# mainboard_v1.net
KiCad netlist of a schematic drawn in EAGLE
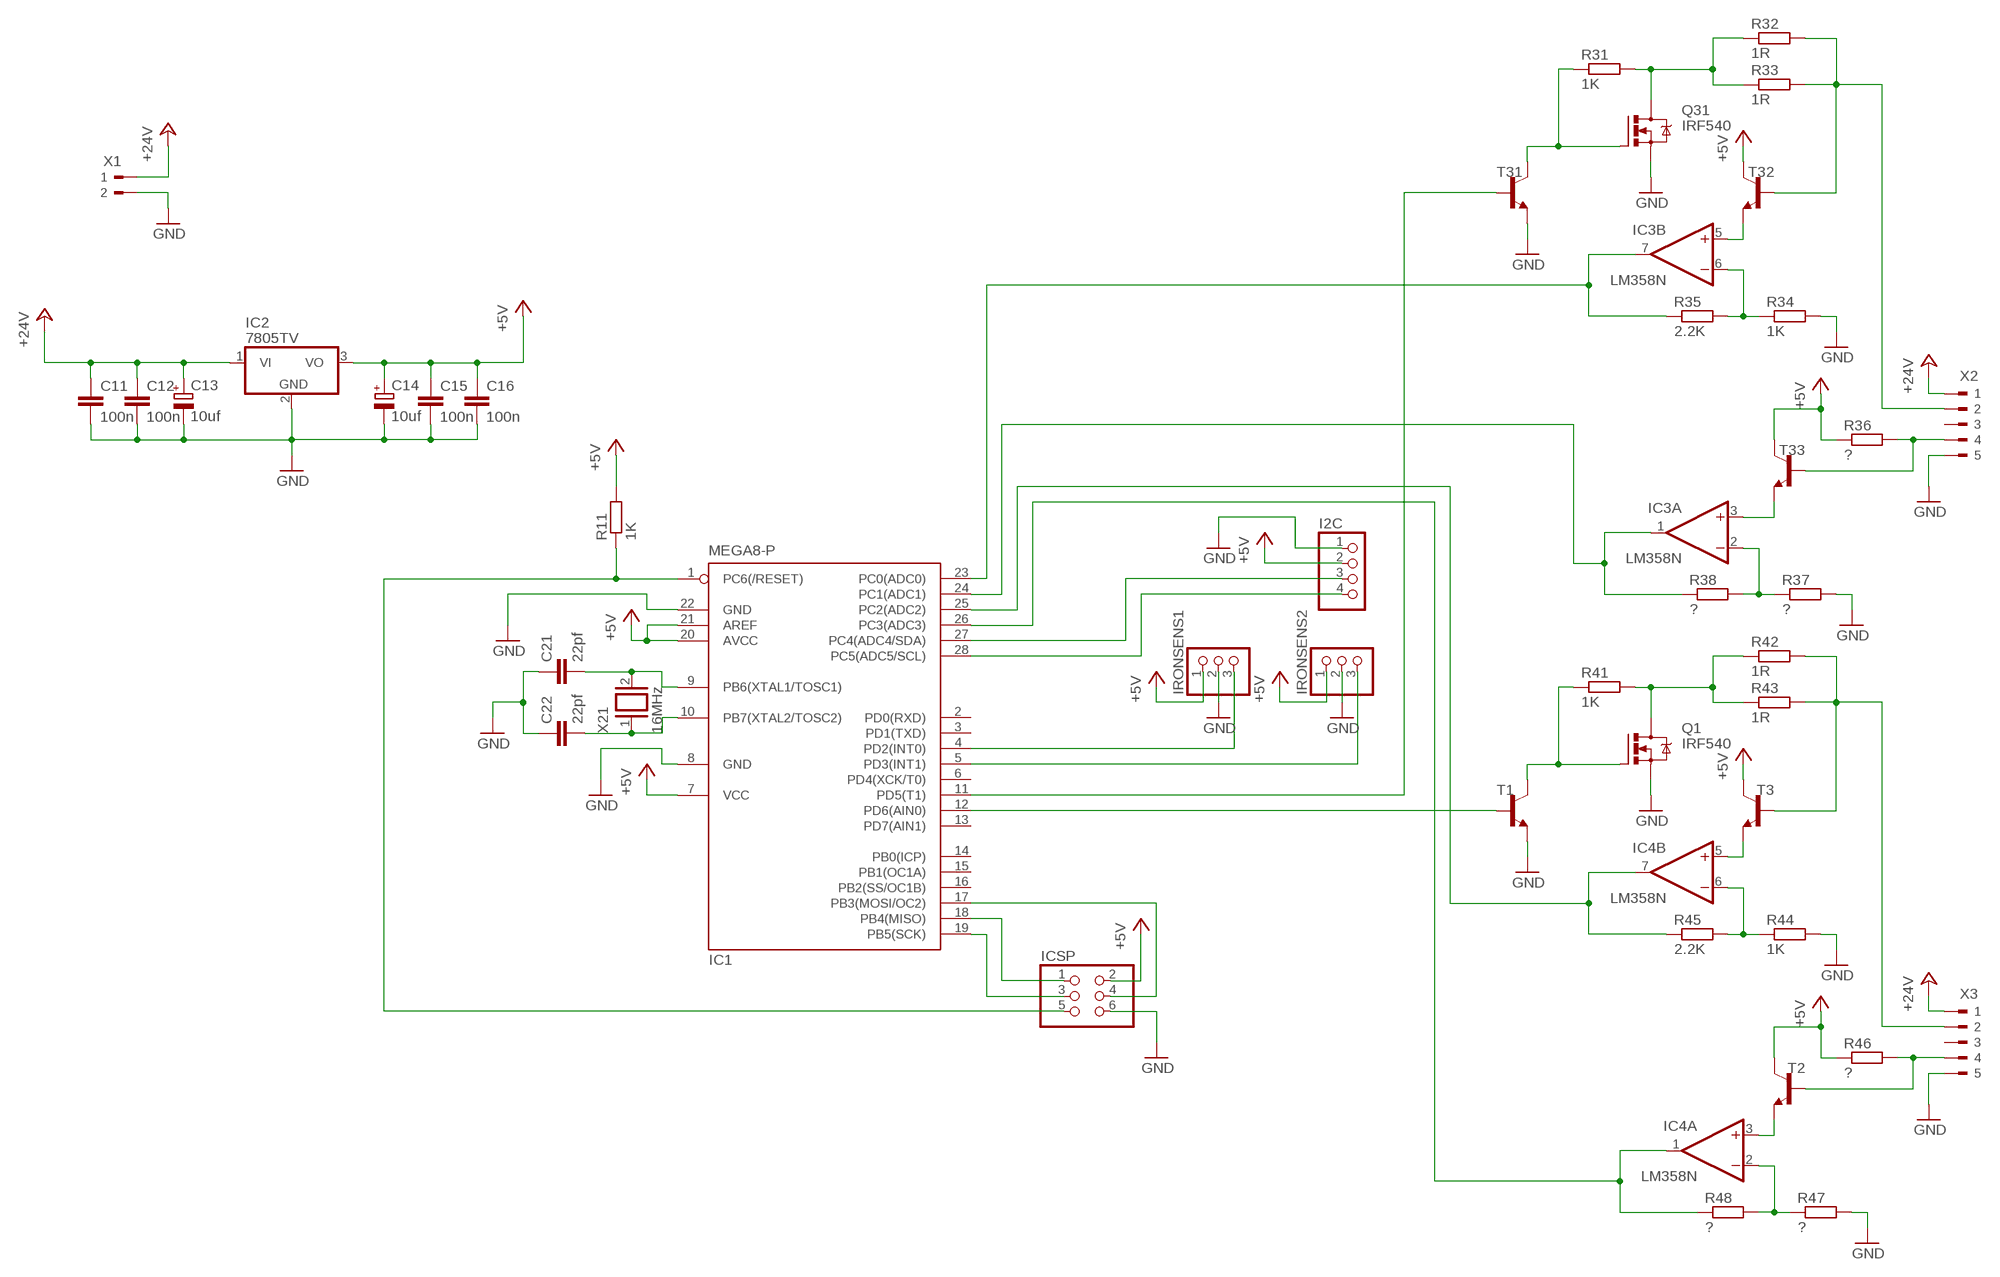
[diagram p0: schematic, sheet 1]

(export (version "E")
  (design (tool "Eeschema 10.0.6"))
  (components
    (comp (ref "C11")
      (value "100n")
      (footprint "eagle-import:C050-030X075")
      (libsource (lib "eagle-import") (part "C-EU050-030X075"))
    )
    (comp (ref "C12")
      (value "100n")
      (footprint "eagle-import:C025-024X044")
      (libsource (lib "eagle-import") (part "C-EU025-024X044"))
    )
    (comp (ref "C13")
      (value "10uf")
      (footprint "eagle-import:E2,5-6E")
      (libsource (lib "eagle-import") (part "CPOL-EUE2,5-6E"))
    )
    (comp (ref "C14")
      (value "10uf")
      (footprint "eagle-import:E2,5-6E")
      (libsource (lib "eagle-import") (part "CPOL-EUE2,5-6E"))
    )
    (comp (ref "C15")
      (value "100n")
      (footprint "eagle-import:C025-024X044")
      (libsource (lib "eagle-import") (part "C-EU025-024X044"))
    )
    (comp (ref "C16")
      (value "100n")
      (footprint "eagle-import:C050-030X075")
      (libsource (lib "eagle-import") (part "C-EU050-030X075"))
    )
    (comp (ref "C21")
      (value "22pf")
      (footprint "eagle-import:C025-025X050")
      (libsource (lib "eagle-import") (part "C-EU025-025X050"))
    )
    (comp (ref "C22")
      (value "22pf")
      (footprint "eagle-import:C025-025X050")
      (libsource (lib "eagle-import") (part "C-EU025-025X050"))
    )
    (comp (ref "I2C")
      (value "PINHD-1X4")
      (footprint "eagle-import:1X04")
      (libsource (lib "eagle-import") (part "PINHD-1X4"))
    )
    (comp (ref "IC1")
      (value "MEGA8-P")
      (footprint "eagle-import:DIL28-3")
      (libsource (lib "eagle-import") (part "MEGA8-P"))
    )
    (comp (ref "IC2")
      (value "7805TV")
      (footprint "eagle-import:TO220V")
      (libsource (lib "eagle-import") (part "78TV05"))
    )
    (comp (ref "IC3")
      (value "LM358N")
      (footprint "eagle-import:DIL08")
      (libsource (lib "eagle-import") (part "LM358N"))
    )
    (comp (ref "IC4")
      (value "LM358N")
      (footprint "eagle-import:DIL08")
      (libsource (lib "eagle-import") (part "LM358N"))
    )
    (comp (ref "ICSP")
      (value "PINHD-2X3")
      (footprint "eagle-import:2X03")
      (libsource (lib "eagle-import") (part "PINHD-2X3"))
    )
    (comp (ref "IRONSENS1")
      (value "PINHD-1X3")
      (footprint "eagle-import:1X03")
      (libsource (lib "eagle-import") (part "PINHD-1X3"))
    )
    (comp (ref "IRONSENS2")
      (value "PINHD-1X3")
      (footprint "eagle-import:1X03")
      (libsource (lib "eagle-import") (part "PINHD-1X3"))
    )
    (comp (ref "Q1")
      (value "IRF540")
      (footprint "eagle-import:TO220BV")
      (libsource (lib "eagle-import") (part "IRF540"))
    )
    (comp (ref "Q31")
      (value "IRF540")
      (footprint "eagle-import:TO220BV")
      (libsource (lib "eagle-import") (part "IRF540"))
    )
    (comp (ref "R11")
      (value "1K")
      (footprint "eagle-import:0204_7")
      (libsource (lib "eagle-import") (part "R-EU_0204/7"))
    )
    (comp (ref "R31")
      (value "1K")
      (footprint "eagle-import:0204_7")
      (libsource (lib "eagle-import") (part "R-EU_0204/7"))
    )
    (comp (ref "R32")
      (value "1R")
      (footprint "eagle-import:R2512")
      (libsource (lib "eagle-import") (part "R-EU_R2512"))
    )
    (comp (ref "R33")
      (value "1R")
      (footprint "eagle-import:0204_7")
      (libsource (lib "eagle-import") (part "R-EU_0204/7"))
    )
    (comp (ref "R34")
      (value "1K")
      (footprint "eagle-import:0204_7")
      (libsource (lib "eagle-import") (part "R-EU_0204/7"))
    )
    (comp (ref "R35")
      (value "2.2K")
      (footprint "eagle-import:0204_7")
      (libsource (lib "eagle-import") (part "R-EU_0204/7"))
    )
    (comp (ref "R36")
      (value "?")
      (footprint "eagle-import:0204_7")
      (libsource (lib "eagle-import") (part "R-EU_0204/7"))
    )
    (comp (ref "R37")
      (value "?")
      (footprint "eagle-import:0204_7")
      (libsource (lib "eagle-import") (part "R-EU_0204/7"))
    )
    (comp (ref "R38")
      (value "?")
      (footprint "eagle-import:0204_7")
      (libsource (lib "eagle-import") (part "R-EU_0204/7"))
    )
    (comp (ref "R41")
      (value "1K")
      (footprint "eagle-import:0204_7")
      (libsource (lib "eagle-import") (part "R-EU_0204/7"))
    )
    (comp (ref "R42")
      (value "1R")
      (footprint "eagle-import:R2512")
      (libsource (lib "eagle-import") (part "R-EU_R2512"))
    )
    (comp (ref "R43")
      (value "1R")
      (footprint "eagle-import:0204_7")
      (libsource (lib "eagle-import") (part "R-EU_0204/7"))
    )
    (comp (ref "R44")
      (value "1K")
      (footprint "eagle-import:0204_7")
      (libsource (lib "eagle-import") (part "R-EU_0204/7"))
    )
    (comp (ref "R45")
      (value "2.2K")
      (footprint "eagle-import:0204_7")
      (libsource (lib "eagle-import") (part "R-EU_0204/7"))
    )
    (comp (ref "R46")
      (value "?")
      (footprint "eagle-import:0204_7")
      (libsource (lib "eagle-import") (part "R-EU_0204/7"))
    )
    (comp (ref "R47")
      (value "?")
      (footprint "eagle-import:0204_7")
      (libsource (lib "eagle-import") (part "R-EU_0204/7"))
    )
    (comp (ref "R48")
      (value "?")
      (footprint "eagle-import:0204_7")
      (libsource (lib "eagle-import") (part "R-EU_0204/7"))
    )
    (comp (ref "T1")
      (value "BC548-NPN-TO92-CBE")
      (footprint "eagle-import:TO92-CBE")
      (libsource (lib "eagle-import") (part "-NPN-TO92-CBEBC548"))
    )
    (comp (ref "T2")
      (value "BC548-NPN-TO92-CBE")
      (footprint "eagle-import:TO92-CBE")
      (libsource (lib "eagle-import") (part "-NPN-TO92-CBEBC548"))
    )
    (comp (ref "T3")
      (value "BC548-NPN-TO92-CBE")
      (footprint "eagle-import:TO92-CBE")
      (libsource (lib "eagle-import") (part "-NPN-TO92-CBEBC548"))
    )
    (comp (ref "T31")
      (value "BC548-NPN-TO92-CBE")
      (footprint "eagle-import:TO92-CBE")
      (libsource (lib "eagle-import") (part "-NPN-TO92-CBEBC548"))
    )
    (comp (ref "T32")
      (value "BC548-NPN-TO92-CBE")
      (footprint "eagle-import:TO92-CBE")
      (libsource (lib "eagle-import") (part "-NPN-TO92-CBEBC548"))
    )
    (comp (ref "T33")
      (value "BC548-NPN-TO92-CBE")
      (footprint "eagle-import:TO92-CBE")
      (libsource (lib "eagle-import") (part "-NPN-TO92-CBEBC548"))
    )
    (comp (ref "X1")
      (value "180-2")
      (footprint "eagle-import:180-2")
      (libsource (lib "eagle-import") (part "180-2"))
    )
    (comp (ref "X2")
      (value "180-5")
      (footprint "eagle-import:180-5")
      (libsource (lib "eagle-import") (part "180-5"))
    )
    (comp (ref "X3")
      (value "180-5")
      (footprint "eagle-import:180-5")
      (libsource (lib "eagle-import") (part "180-5"))
    )
    (comp (ref "X21")
      (value "16MHz")
      (footprint "eagle-import:QS")
      (libsource (lib "eagle-import") (part "XTAL/S"))
    )
  )
  (nets
    (net (code "1") (name "+5V") (class "Default")
      (node (ref "C14") (pin "+") (pinfunction "+_+") (pintype "passive"))
      (node (ref "C15") (pin "1") (pinfunction "1_1") (pintype "passive"))
      (node (ref "C16") (pin "1") (pinfunction "1_1") (pintype "passive"))
      (node (ref "I2C") (pin "2") (pinfunction "2_2") (pintype "passive"))
      (node (ref "IC1") (pin "20") (pinfunction "AVCC_20") (pintype "power_in"))
      (node (ref "IC1") (pin "21") (pinfunction "AREF_21") (pintype "passive"))
      (node (ref "IC1") (pin "7") (pinfunction "VCC_7") (pintype "power_in"))
      (node (ref "IC2") (pin "3") (pinfunction "VO_3") (pintype "passive"))
      (node (ref "ICSP") (pin "2") (pinfunction "2_2") (pintype "passive"))
      (node (ref "IRONSENS1") (pin "1") (pinfunction "1_1") (pintype "passive"))
      (node (ref "IRONSENS2") (pin "1") (pinfunction "1_1") (pintype "passive"))
      (node (ref "R11") (pin "2") (pinfunction "2_2") (pintype "passive"))
      (node (ref "R36") (pin "1") (pinfunction "1_1") (pintype "passive"))
      (node (ref "R46") (pin "1") (pinfunction "1_1") (pintype "passive"))
      (node (ref "T2") (pin "C") (pinfunction "C_C") (pintype "passive"))
      (node (ref "T3") (pin "C") (pinfunction "C_C") (pintype "passive"))
      (node (ref "T32") (pin "C") (pinfunction "C_C") (pintype "passive"))
      (node (ref "T33") (pin "C") (pinfunction "C_C") (pintype "passive"))
    )
    (net (code "2") (name "+24V") (class "Default")
      (node (ref "C11") (pin "1") (pinfunction "1_1") (pintype "passive"))
      (node (ref "C12") (pin "1") (pinfunction "1_1") (pintype "passive"))
      (node (ref "C13") (pin "+") (pinfunction "+_+") (pintype "passive"))
      (node (ref "IC2") (pin "1") (pinfunction "VI_1") (pintype "input"))
      (node (ref "X1") (pin "1") (pinfunction "1_1") (pintype "passive"))
      (node (ref "X2") (pin "1") (pinfunction "1_1") (pintype "passive"))
      (node (ref "X3") (pin "1") (pinfunction "1_1") (pintype "passive"))
    )
    (net (code "3") (name "GND") (class "Default")
      (node (ref "C11") (pin "2") (pinfunction "2_2") (pintype "passive"))
      (node (ref "C12") (pin "2") (pinfunction "2_2") (pintype "passive"))
      (node (ref "C13") (pin "-") (pinfunction "-_-") (pintype "passive"))
      (node (ref "C14") (pin "-") (pinfunction "-_-") (pintype "passive"))
      (node (ref "C15") (pin "2") (pinfunction "2_2") (pintype "passive"))
      (node (ref "C16") (pin "2") (pinfunction "2_2") (pintype "passive"))
      (node (ref "C21") (pin "1") (pinfunction "1_1") (pintype "passive"))
      (node (ref "C22") (pin "1") (pinfunction "1_1") (pintype "passive"))
      (node (ref "I2C") (pin "1") (pinfunction "1_1") (pintype "passive"))
      (node (ref "IC1") (pin "22") (pinfunction "GND_22") (pintype "power_in"))
      (node (ref "IC1") (pin "8") (pinfunction "GND_8") (pintype "power_in"))
      (node (ref "IC2") (pin "2") (pinfunction "GND_2") (pintype "passive"))
      (node (ref "ICSP") (pin "6") (pinfunction "6_6") (pintype "passive"))
      (node (ref "IRONSENS1") (pin "2") (pinfunction "2_2") (pintype "passive"))
      (node (ref "IRONSENS2") (pin "2") (pinfunction "2_2") (pintype "passive"))
      (node (ref "Q1") (pin "S") (pinfunction "S_S") (pintype "passive"))
      (node (ref "Q31") (pin "S") (pinfunction "S_S") (pintype "passive"))
      (node (ref "R34") (pin "2") (pinfunction "2_2") (pintype "passive"))
      (node (ref "R37") (pin "2") (pinfunction "2_2") (pintype "passive"))
      (node (ref "R44") (pin "2") (pinfunction "2_2") (pintype "passive"))
      (node (ref "R47") (pin "2") (pinfunction "2_2") (pintype "passive"))
      (node (ref "T1") (pin "E") (pinfunction "E_E") (pintype "passive"))
      (node (ref "T31") (pin "E") (pinfunction "E_E") (pintype "passive"))
      (node (ref "X1") (pin "2") (pinfunction "2_2") (pintype "passive"))
      (node (ref "X2") (pin "5") (pinfunction "5_5") (pintype "passive"))
      (node (ref "X3") (pin "5") (pinfunction "5_5") (pintype "passive"))
    )
    (net (code "4") (name "Net-(IC1-PB3(MOSI{slash}OC2))") (class "Default")
      (node (ref "IC1") (pin "17") (pinfunction "PB3(MOSI/OC2)_17") (pintype "bidirectional"))
      (node (ref "ICSP") (pin "4") (pinfunction "4_4") (pintype "passive"))
    )
    (net (code "5") (name "Net-(IC1-PB4(MISO))") (class "Default")
      (node (ref "IC1") (pin "18") (pinfunction "PB4(MISO)_18") (pintype "bidirectional"))
      (node (ref "ICSP") (pin "1") (pinfunction "1_1") (pintype "passive"))
    )
    (net (code "6") (name "Net-(IC1-PB5(SCK))") (class "Default")
      (node (ref "IC1") (pin "19") (pinfunction "PB5(SCK)_19") (pintype "bidirectional"))
      (node (ref "ICSP") (pin "3") (pinfunction "3_3") (pintype "passive"))
    )
    (net (code "7") (name "Net-(IC1-PB6(XTAL1{slash}TOSC1))") (class "Default")
      (node (ref "C21") (pin "2") (pinfunction "2_2") (pintype "passive"))
      (node (ref "IC1") (pin "9") (pinfunction "PB6(XTAL1/TOSC1)_9") (pintype "bidirectional"))
      (node (ref "X21") (pin "2") (pinfunction "2_2") (pintype "passive"))
    )
    (net (code "8") (name "Net-(IC1-PB7(XTAL2{slash}TOSC2))") (class "Default")
      (node (ref "C22") (pin "2") (pinfunction "2_2") (pintype "passive"))
      (node (ref "IC1") (pin "10") (pinfunction "PB7(XTAL2/TOSC2)_10") (pintype "bidirectional"))
      (node (ref "X21") (pin "1") (pinfunction "1_1") (pintype "passive"))
    )
    (net (code "9") (name "Net-(IC1-PC0(ADC0))") (class "Default")
      (node (ref "IC1") (pin "23") (pinfunction "PC0(ADC0)_23") (pintype "bidirectional"))
      (node (ref "IC3") (pin "7") (pinfunction "OUT_7") (pintype "output"))
      (node (ref "R35") (pin "1") (pinfunction "1_1") (pintype "passive"))
    )
    (net (code "10") (name "Net-(IC1-PC1(ADC1))") (class "Default")
      (node (ref "IC1") (pin "24") (pinfunction "PC1(ADC1)_24") (pintype "bidirectional"))
      (node (ref "IC3") (pin "1") (pinfunction "OUT_1") (pintype "output"))
      (node (ref "R38") (pin "1") (pinfunction "1_1") (pintype "passive"))
    )
    (net (code "11") (name "Net-(IC1-PC2(ADC2))") (class "Default")
      (node (ref "IC1") (pin "25") (pinfunction "PC2(ADC2)_25") (pintype "bidirectional"))
      (node (ref "IC4") (pin "7") (pinfunction "OUT_7") (pintype "output"))
      (node (ref "R45") (pin "1") (pinfunction "1_1") (pintype "passive"))
    )
    (net (code "12") (name "Net-(IC1-PC3(ADC3))") (class "Default")
      (node (ref "IC1") (pin "26") (pinfunction "PC3(ADC3)_26") (pintype "bidirectional"))
      (node (ref "IC4") (pin "1") (pinfunction "OUT_1") (pintype "output"))
      (node (ref "R48") (pin "1") (pinfunction "1_1") (pintype "passive"))
    )
    (net (code "13") (name "Net-(IC1-PC4(ADC4{slash}SDA))") (class "Default")
      (node (ref "I2C") (pin "3") (pinfunction "3_3") (pintype "passive"))
      (node (ref "IC1") (pin "27") (pinfunction "PC4(ADC4/SDA)_27") (pintype "bidirectional"))
    )
    (net (code "14") (name "Net-(IC1-PC5(ADC5{slash}SCL))") (class "Default")
      (node (ref "I2C") (pin "4") (pinfunction "4_4") (pintype "passive"))
      (node (ref "IC1") (pin "28") (pinfunction "PC5(ADC5/SCL)_28") (pintype "bidirectional"))
    )
    (net (code "15") (name "Net-(IC1-PC6({slash}RESET))") (class "Default")
      (node (ref "IC1") (pin "1") (pinfunction "PC6(/RESET)_1") (pintype "bidirectional"))
      (node (ref "ICSP") (pin "5") (pinfunction "5_5") (pintype "passive"))
      (node (ref "R11") (pin "1") (pinfunction "1_1") (pintype "passive"))
    )
    (net (code "16") (name "Net-(IC1-PD2(INT0))") (class "Default")
      (node (ref "IC1") (pin "4") (pinfunction "PD2(INT0)_4") (pintype "bidirectional"))
      (node (ref "IRONSENS1") (pin "3") (pinfunction "3_3") (pintype "passive"))
    )
    (net (code "17") (name "Net-(IC1-PD3(INT1))") (class "Default")
      (node (ref "IC1") (pin "5") (pinfunction "PD3(INT1)_5") (pintype "bidirectional"))
      (node (ref "IRONSENS2") (pin "3") (pinfunction "3_3") (pintype "passive"))
    )
    (net (code "18") (name "Net-(IC1-PD5(T1))") (class "Default")
      (node (ref "IC1") (pin "11") (pinfunction "PD5(T1)_11") (pintype "bidirectional"))
      (node (ref "T31") (pin "B") (pinfunction "B_B") (pintype "passive"))
    )
    (net (code "19") (name "Net-(IC1-PD6(AIN0))") (class "Default")
      (node (ref "IC1") (pin "12") (pinfunction "PD6(AIN0)_12") (pintype "bidirectional"))
      (node (ref "T1") (pin "B") (pinfunction "B_B") (pintype "passive"))
    )
    (net (code "20") (name "Net-(IC3A-+IN)") (class "Default")
      (node (ref "IC3") (pin "3") (pinfunction "+IN_3") (pintype "input"))
      (node (ref "T33") (pin "E") (pinfunction "E_E") (pintype "passive"))
    )
    (net (code "21") (name "Net-(IC3A--IN)") (class "Default")
      (node (ref "IC3") (pin "2") (pinfunction "-IN_2") (pintype "input"))
      (node (ref "R37") (pin "1") (pinfunction "1_1") (pintype "passive"))
      (node (ref "R38") (pin "2") (pinfunction "2_2") (pintype "passive"))
    )
    (net (code "22") (name "Net-(IC3B-+IN)") (class "Default")
      (node (ref "IC3") (pin "5") (pinfunction "+IN_5") (pintype "input"))
      (node (ref "T32") (pin "E") (pinfunction "E_E") (pintype "passive"))
    )
    (net (code "23") (name "Net-(IC3B--IN)") (class "Default")
      (node (ref "IC3") (pin "6") (pinfunction "-IN_6") (pintype "input"))
      (node (ref "R34") (pin "1") (pinfunction "1_1") (pintype "passive"))
      (node (ref "R35") (pin "2") (pinfunction "2_2") (pintype "passive"))
    )
    (net (code "24") (name "Net-(IC4A-+IN)") (class "Default")
      (node (ref "IC4") (pin "3") (pinfunction "+IN_3") (pintype "input"))
      (node (ref "T2") (pin "E") (pinfunction "E_E") (pintype "passive"))
    )
    (net (code "25") (name "Net-(IC4A--IN)") (class "Default")
      (node (ref "IC4") (pin "2") (pinfunction "-IN_2") (pintype "input"))
      (node (ref "R47") (pin "1") (pinfunction "1_1") (pintype "passive"))
      (node (ref "R48") (pin "2") (pinfunction "2_2") (pintype "passive"))
    )
    (net (code "26") (name "Net-(IC4B-+IN)") (class "Default")
      (node (ref "IC4") (pin "5") (pinfunction "+IN_5") (pintype "input"))
      (node (ref "T3") (pin "E") (pinfunction "E_E") (pintype "passive"))
    )
    (net (code "27") (name "Net-(IC4B--IN)") (class "Default")
      (node (ref "IC4") (pin "6") (pinfunction "-IN_6") (pintype "input"))
      (node (ref "R44") (pin "1") (pinfunction "1_1") (pintype "passive"))
      (node (ref "R45") (pin "2") (pinfunction "2_2") (pintype "passive"))
    )
    (net (code "28") (name "Net-(Q1-PadD)") (class "Default")
      (node (ref "Q1") (pin "D") (pinfunction "D_D") (pintype "passive"))
      (node (ref "R41") (pin "2") (pinfunction "2_2") (pintype "passive"))
      (node (ref "R42") (pin "1") (pinfunction "1_1") (pintype "passive"))
      (node (ref "R43") (pin "1") (pinfunction "1_1") (pintype "passive"))
    )
    (net (code "29") (name "Net-(Q1-PadG)") (class "Default")
      (node (ref "Q1") (pin "G") (pinfunction "G_G") (pintype "passive"))
      (node (ref "R41") (pin "1") (pinfunction "1_1") (pintype "passive"))
      (node (ref "T1") (pin "C") (pinfunction "C_C") (pintype "passive"))
    )
    (net (code "30") (name "Net-(Q31-PadD)") (class "Default")
      (node (ref "Q31") (pin "D") (pinfunction "D_D") (pintype "passive"))
      (node (ref "R31") (pin "2") (pinfunction "2_2") (pintype "passive"))
      (node (ref "R32") (pin "1") (pinfunction "1_1") (pintype "passive"))
      (node (ref "R33") (pin "1") (pinfunction "1_1") (pintype "passive"))
    )
    (net (code "31") (name "Net-(Q31-PadG)") (class "Default")
      (node (ref "Q31") (pin "G") (pinfunction "G_G") (pintype "passive"))
      (node (ref "R31") (pin "1") (pinfunction "1_1") (pintype "passive"))
      (node (ref "T31") (pin "C") (pinfunction "C_C") (pintype "passive"))
    )
    (net (code "32") (name "Net-(R32-Pad2)") (class "Default")
      (node (ref "R32") (pin "2") (pinfunction "2_2") (pintype "passive"))
      (node (ref "R33") (pin "2") (pinfunction "2_2") (pintype "passive"))
      (node (ref "T32") (pin "B") (pinfunction "B_B") (pintype "passive"))
      (node (ref "X2") (pin "2") (pinfunction "2_2") (pintype "passive"))
    )
    (net (code "33") (name "Net-(R36-Pad2)") (class "Default")
      (node (ref "R36") (pin "2") (pinfunction "2_2") (pintype "passive"))
      (node (ref "T33") (pin "B") (pinfunction "B_B") (pintype "passive"))
      (node (ref "X2") (pin "4") (pinfunction "4_4") (pintype "passive"))
    )
    (net (code "34") (name "Net-(R42-Pad2)") (class "Default")
      (node (ref "R42") (pin "2") (pinfunction "2_2") (pintype "passive"))
      (node (ref "R43") (pin "2") (pinfunction "2_2") (pintype "passive"))
      (node (ref "T3") (pin "B") (pinfunction "B_B") (pintype "passive"))
      (node (ref "X3") (pin "2") (pinfunction "2_2") (pintype "passive"))
    )
    (net (code "35") (name "Net-(R46-Pad2)") (class "Default")
      (node (ref "R46") (pin "2") (pinfunction "2_2") (pintype "passive"))
      (node (ref "T2") (pin "B") (pinfunction "B_B") (pintype "passive"))
      (node (ref "X3") (pin "4") (pinfunction "4_4") (pintype "passive"))
    )
    (net (code "36") (name "unconnected-(IC1-PB0(ICP)-Pad14)") (class "Default")
      (node (ref "IC1") (pin "14") (pinfunction "PB0(ICP)_14") (pintype "bidirectional"))
    )
    (net (code "37") (name "unconnected-(IC1-PB1(OC1A)-Pad15)") (class "Default")
      (node (ref "IC1") (pin "15") (pinfunction "PB1(OC1A)_15") (pintype "bidirectional"))
    )
    (net (code "38") (name "unconnected-(IC1-PB2(SS{slash}OC1B)-Pad16)") (class "Default")
      (node (ref "IC1") (pin "16") (pinfunction "PB2(SS/OC1B)_16") (pintype "bidirectional"))
    )
    (net (code "39") (name "unconnected-(IC1-PD0(RXD)-Pad2)") (class "Default")
      (node (ref "IC1") (pin "2") (pinfunction "PD0(RXD)_2") (pintype "bidirectional"))
    )
    (net (code "40") (name "unconnected-(IC1-PD1(TXD)-Pad3)") (class "Default")
      (node (ref "IC1") (pin "3") (pinfunction "PD1(TXD)_3") (pintype "bidirectional"))
    )
    (net (code "41") (name "unconnected-(IC1-PD4(XCK{slash}T0)-Pad6)") (class "Default")
      (node (ref "IC1") (pin "6") (pinfunction "PD4(XCK/T0)_6") (pintype "bidirectional"))
    )
    (net (code "42") (name "unconnected-(IC1-PD7(AIN1)-Pad13)") (class "Default")
      (node (ref "IC1") (pin "13") (pinfunction "PD7(AIN1)_13") (pintype "bidirectional"))
    )
    (net (code "43") (name "unconnected-(X2-Pad3)") (class "Default")
      (node (ref "X2") (pin "3") (pinfunction "3_3") (pintype "passive"))
    )
    (net (code "44") (name "unconnected-(X3-Pad3)") (class "Default")
      (node (ref "X3") (pin "3") (pinfunction "3_3") (pintype "passive"))
    )
  )
)
